# Connectors.net
KiCad netlist of a schematic drawn in Altium Designer
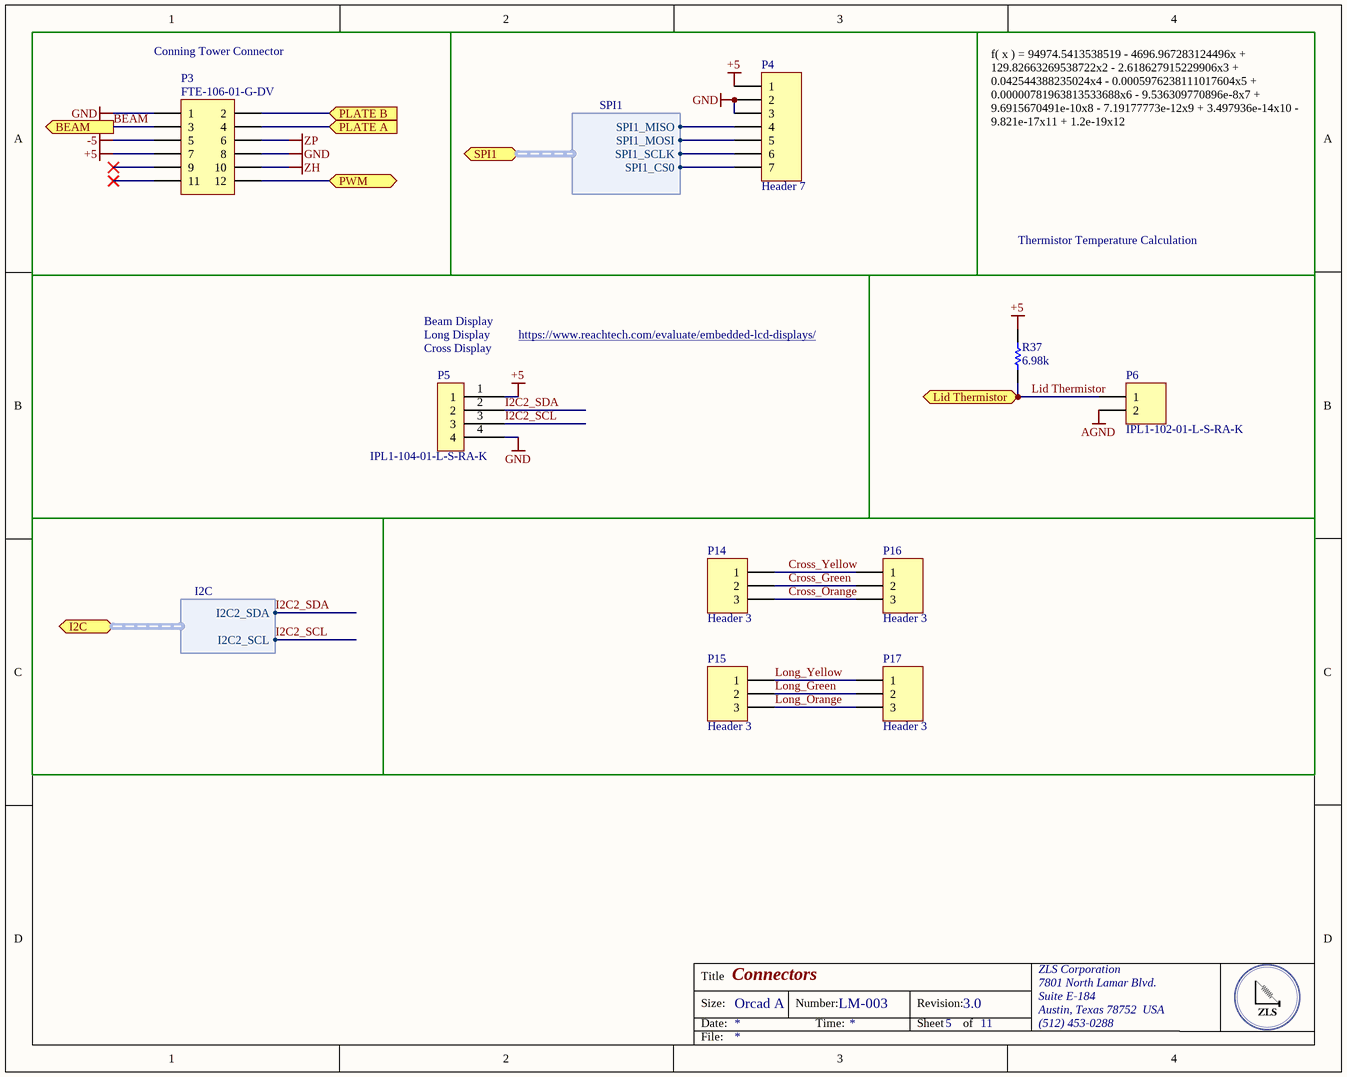
[diagram p0: Connectors.SchDoc]

(export (version "E")
  (design (tool "Eeschema 10.0.6"))
  (components
    (comp (ref "P3")
      (value "FTE-106-01-G-DV")
      (footprint "FTSH-106-01")
      (description "Header, 6-Pin, Dual row")
      (fields (field (name "MANUFACTURER") "Samtec") (field (name "PUBLISHER") "Altium Limited"))
      (libsource (lib "Conning Tower Adapter") (part "Header 6X2"))
    )
    (comp (ref "P4")
      (value "Header 7")
      (footprint "HDR1X7")
      (description "Header, 7-Pin")
      (fields (field (name "PUBLISHER") "Altium Limited"))
      (libsource (lib "Miscellaneous Connectors") (part "Header 7"))
    )
    (comp (ref "P5")
      (value "IPL1-104-01-L-S-RA-K")
      (footprint "IPL1-104-01")
      (description ".100 TERMINAL ASSY")
      (libsource (lib "ZLS_LIB") (part "53047-0410"))
    )
    (comp (ref "P6")
      (value "IPL1-102-01-L-S-RA-K")
      (footprint "IPL1-102-01")
      (description "CONN SHROUDED PWR HEADER 2POS")
      (libsource (lib "Miscellaneous Connectors") (part "Header 2H"))
    )
    (comp (ref "P14")
      (value "Header 3")
      (footprint "HDR1X3")
      (description "Header, 3-Pin")
      (fields (field (name "PUBLISHER") "Altium Limited"))
      (libsource (lib "Miscellaneous Connectors") (part "Header 3"))
    )
    (comp (ref "P15")
      (value "Header 3")
      (footprint "HDR1X3")
      (description "Header, 3-Pin")
      (fields (field (name "PUBLISHER") "Altium Limited"))
      (libsource (lib "Miscellaneous Connectors") (part "Header 3"))
    )
    (comp (ref "P16")
      (value "Header 3")
      (footprint "TLW-103-01-G-S-RA")
      (description "Header, 3-Pin")
      (fields (field (name "PUBLISHER") "Altium Limited"))
      (libsource (lib "") (part "Header 3_1"))
    )
    (comp (ref "P17")
      (value "Header 3")
      (footprint "TLW-103-01-G-S-RA")
      (description "Header, 3-Pin")
      (fields (field (name "PUBLISHER") "Altium Limited"))
      (libsource (lib "") (part "Header 3_1"))
    )
    (comp (ref "R37")
      (value "6K98 1% 0805(2012)")
      (footprint "RESC0805(2012)_N")
      (description "6K98 0.125W 1% 0805 (2012 Metric)  SMD")
      (fields
        (field (name "MANUFACTURER") "Vishay Dale")
        (field (name "MANUFACTURER PART NUMBER") "CRCW08056K98FKEA")
        (field (name "RESISTANCE (OHMS)") "6.98k")
      )
      (libsource (lib "Altium Content Vault") (part "CMP-1013-00606-1"))
    )
  )
  (nets
    (net (code "3") (name "+5") (class "Default")
      (node (ref "P3") (pin "7") (pinfunction "7_7") (pintype "passive"))
      (node (ref "P4") (pin "1") (pinfunction "1_1") (pintype "passive"))
      (node (ref "P5") (pin "1") (pinfunction "1_1") (pintype "passive"))
      (node (ref "R37") (pin "2") (pinfunction "2_2") (pintype "passive"))
    )
    (net (code "4") (name "-5") (class "Default")
      (node (ref "P3") (pin "5") (pinfunction "5_5") (pintype "passive"))
    )
    (net (code "5") (name "/BEAM") (class "Default")
      (node (ref "P3") (pin "3") (pinfunction "3_3") (pintype "passive"))
    )
    (net (code "6") (name "/Cross_Green") (class "Default")
      (node (ref "P14") (pin "2") (pinfunction "2_2") (pintype "passive"))
      (node (ref "P16") (pin "2") (pinfunction "2_2") (pintype "passive"))
    )
    (net (code "7") (name "/Cross_Orange") (class "Default")
      (node (ref "P14") (pin "3") (pinfunction "3_3") (pintype "passive"))
      (node (ref "P16") (pin "3") (pinfunction "3_3") (pintype "passive"))
    )
    (net (code "8") (name "/Cross_Yellow") (class "Default")
      (node (ref "P14") (pin "1") (pinfunction "1_1") (pintype "passive"))
      (node (ref "P16") (pin "1") (pinfunction "1_1") (pintype "passive"))
    )
    (net (code "9") (name "/I2C2_SCL") (class "Default")
      (node (ref "P5") (pin "3") (pinfunction "3_3") (pintype "passive"))
    )
    (net (code "10") (name "/I2C2_SDA") (class "Default")
      (node (ref "P5") (pin "2") (pinfunction "2_2") (pintype "passive"))
    )
    (net (code "11") (name "/Lid Thermistor") (class "Default")
      (node (ref "P6") (pin "1") (pinfunction "1_1") (pintype "passive"))
      (node (ref "R37") (pin "1") (pinfunction "1_1") (pintype "passive"))
    )
    (net (code "12") (name "/Long_Green") (class "Default")
      (node (ref "P15") (pin "2") (pinfunction "2_2") (pintype "passive"))
      (node (ref "P17") (pin "2") (pinfunction "2_2") (pintype "passive"))
    )
    (net (code "13") (name "/Long_Orange") (class "Default")
      (node (ref "P15") (pin "3") (pinfunction "3_3") (pintype "passive"))
      (node (ref "P17") (pin "3") (pinfunction "3_3") (pintype "passive"))
    )
    (net (code "14") (name "/Long_Yellow") (class "Default")
      (node (ref "P15") (pin "1") (pinfunction "1_1") (pintype "passive"))
      (node (ref "P17") (pin "1") (pinfunction "1_1") (pintype "passive"))
    )
    (net (code "15") (name "/PLATE A") (class "Default")
      (node (ref "P3") (pin "4") (pinfunction "4_4") (pintype "passive"))
    )
    (net (code "16") (name "/PLATE B") (class "Default")
      (node (ref "P3") (pin "2") (pinfunction "2_2") (pintype "passive"))
    )
    (net (code "17") (name "/PWM") (class "Default")
      (node (ref "P3") (pin "12") (pinfunction "12_12") (pintype "passive"))
    )
    (net (code "18") (name "/SPI1_CS0") (class "Default")
      (node (ref "P4") (pin "7") (pinfunction "7_7") (pintype "passive"))
    )
    (net (code "19") (name "/SPI1_MISO") (class "Default")
      (node (ref "P4") (pin "4") (pinfunction "4_4") (pintype "passive"))
    )
    (net (code "20") (name "/SPI1_MOSI") (class "Default")
      (node (ref "P4") (pin "5") (pinfunction "5_5") (pintype "passive"))
    )
    (net (code "21") (name "/SPI1_SCLK") (class "Default")
      (node (ref "P4") (pin "6") (pinfunction "6_6") (pintype "passive"))
    )
    (net (code "24") (name "AGND") (class "Default")
      (node (ref "P6") (pin "2") (pinfunction "2_2") (pintype "passive"))
    )
    (net (code "25") (name "GND") (class "Default")
      (node (ref "P3") (pin "1") (pinfunction "1_1") (pintype "passive"))
      (node (ref "P3") (pin "8") (pinfunction "8_8") (pintype "passive"))
      (node (ref "P4") (pin "2") (pinfunction "2_2") (pintype "passive"))
      (node (ref "P4") (pin "3") (pinfunction "3_3") (pintype "passive"))
      (node (ref "P5") (pin "4") (pinfunction "4_4") (pintype "passive"))
    )
    (net (code "26") (name "ZH") (class "Default")
      (node (ref "P3") (pin "10") (pinfunction "10_10") (pintype "passive"))
    )
    (net (code "27") (name "ZP") (class "Default")
      (node (ref "P3") (pin "6") (pinfunction "6_6") (pintype "passive"))
    )
    (net (code "28") (name "unconnected-(P3-Pad9)") (class "Default")
      (node (ref "P3") (pin "9") (pinfunction "9_9") (pintype "passive+no_connect"))
    )
    (net (code "29") (name "unconnected-(P3-Pad11)") (class "Default")
      (node (ref "P3") (pin "11") (pinfunction "11_11") (pintype "passive+no_connect"))
    )
  )
)
